# ZOWI_Main_Board_Peripherals.net
KiCad netlist of a schematic drawn in Altium Designer
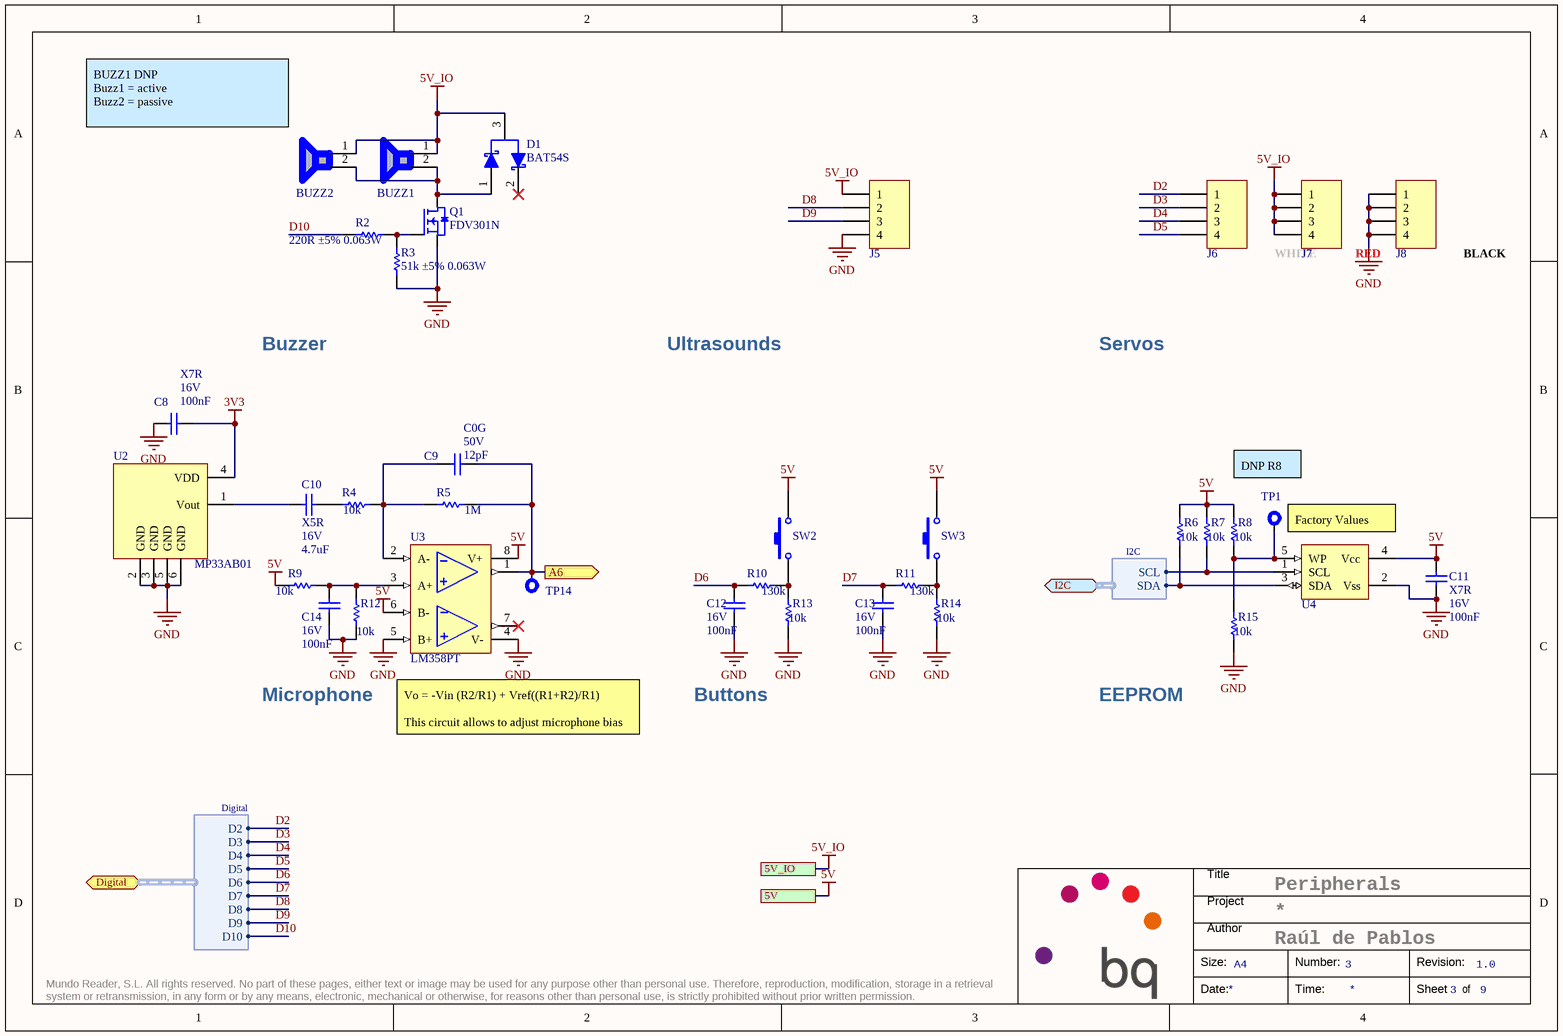
[diagram p0: ZOWI_Main_Board_Peripherals.SchDoc]

(export (version "E")
  (design (tool "Eeschema 10.0.6"))
  (components
    (comp (ref "BUZZ1")
      (value "BUZZER")
      (footprint "KXG1205C")
      (description "Buzzer")
      (fields (field (name "MANUFACTURER") "Kingstate Elect.") (field (name "PART NUMBER") "KXG1205C"))
      (libsource (lib "Electromechanical") (part "BUZZER"))
    )
    (comp (ref "BUZZ2")
      (value "BUZZER")
      (footprint "BUZZER_12")
      (description "Buzzer")
      (fields (field (name "MANUFACTURER") "Kingstate Elect.") (field (name "PART NUMBER") "KXG1205"))
      (libsource (lib "Electromechanical") (part "BUZZER"))
    )
    (comp (ref "C8")
      (value "Capacitor")
      (footprint "C0402")
      (description "Capacitor SMD")
      (fields
        (field (name "DIELECTRIC") "X7R")
        (field (name "VOLTAGE") "16V")
        (field (name "CAPACITANCE") "100nF")
        (field (name "PART NUMBER") "C0402_100nF_16V_±10%")
        (field (name "TOLERANCE") "±10%")
      )
      (libsource (lib "Pasives_Capacitor_SMD") (part "Capacitor"))
    )
    (comp (ref "C9")
      (value "Capacitor")
      (footprint "C0402")
      (description "Capacitor SMD")
      (fields
        (field (name "DIELECTRIC") "C0G")
        (field (name "VOLTAGE") "50V")
        (field (name "CAPACITANCE") "12pF")
        (field (name "PART NUMBER") "C0402_12pF_50V_±5%")
        (field (name "TOLERANCE") "±5%")
      )
      (libsource (lib "Pasives_Capacitor_SMD") (part "Capacitor"))
    )
    (comp (ref "C10")
      (value "Capacitor")
      (footprint "C0603")
      (description "Capacitor SMD")
      (fields
        (field (name "DIELECTRIC") "X5R")
        (field (name "VOLTAGE") "16V")
        (field (name "CAPACITANCE") "4.7uF")
        (field (name "PART NUMBER") "C0603_4.7uF_16V_±10%")
        (field (name "TOLERANCE") "±10%")
      )
      (libsource (lib "Pasives_Capacitor_SMD") (part "Capacitor"))
    )
    (comp (ref "C11")
      (value "Capacitor")
      (footprint "C0402")
      (description "Capacitor SMD")
      (fields
        (field (name "DIELECTRIC") "X7R")
        (field (name "VOLTAGE") "16V")
        (field (name "CAPACITANCE") "100nF")
        (field (name "PART NUMBER") "C0402_100nF_16V_±10%")
        (field (name "TOLERANCE") "±10%")
      )
      (libsource (lib "Pasives_Capacitor_SMD") (part "Capacitor"))
    )
    (comp (ref "C12")
      (value "Capacitor")
      (footprint "C0402")
      (description "Capacitor SMD")
      (fields
        (field (name "VOLTAGE") "16V")
        (field (name "CAPACITANCE") "100nF")
        (field (name "PART NUMBER") "C0402_100nF_16V_±10%")
        (field (name "TOLERANCE") "±10%")
      )
      (libsource (lib "Pasives_Capacitor_SMD") (part "Capacitor"))
    )
    (comp (ref "C13")
      (value "Capacitor")
      (footprint "C0402")
      (description "Capacitor SMD")
      (fields
        (field (name "VOLTAGE") "16V")
        (field (name "CAPACITANCE") "100nF")
        (field (name "PART NUMBER") "C0402_100nF_16V_±10%")
        (field (name "TOLERANCE") "±10%")
      )
      (libsource (lib "Pasives_Capacitor_SMD") (part "Capacitor"))
    )
    (comp (ref "C14")
      (value "Capacitor")
      (footprint "C0402")
      (description "Capacitor SMD")
      (fields
        (field (name "VOLTAGE") "16V")
        (field (name "CAPACITANCE") "100nF")
        (field (name "PART NUMBER") "C0402_100nF_16V_±10%")
        (field (name "TOLERANCE") "±10%")
      )
      (libsource (lib "Pasives_Capacitor_SMD") (part "Capacitor"))
    )
    (comp (ref "D1")
      (value "BAT54S")
      (footprint "SOT23-3")
      (description "Dual Schottky Diode")
      (fields (field (name "MANUFACTURER") "NXP"))
      (libsource (lib "Semiconductors_Diodes") (part "Dual Schottky"))
    )
    (comp (ref "J5")
      (value "1x4 pin Header 2.54mm")
      (footprint "1x4 Pin Header 2.54")
      (description "Connector, 1x4 pin Header 2.54mm")
      (fields (field (name "MANUFACTURER") "Samtec") (field (name "PART NUMBER") "CON_PH_THT2.54_4"))
      (libsource (lib "Conectores_PinHeader_2.54") (part "1x4 pin Header 2.54mm"))
    )
    (comp (ref "J6")
      (value "1x4 pin Header 2.54mm")
      (footprint "1x4 Pin Header 2.54")
      (description "Connector, 1x4 pin Header 2.54mm")
      (fields (field (name "MANUFACTURER") "Samtec") (field (name "PART NUMBER") "CON_PH_THT2.54_4 Natural"))
      (libsource (lib "Conectores_PinHeader_2.54") (part "1x4 pin Header 2.54mm"))
    )
    (comp (ref "J7")
      (value "1x4 pin Header 2.54mm")
      (footprint "1x4 Pin Header 2.54")
      (description "Connector, 1x4 pin Header 2.54mm")
      (fields (field (name "MANUFACTURER") "Samtec") (field (name "PART NUMBER") "CON_PH_THT2.54_4 Red"))
      (libsource (lib "Conectores_PinHeader_2.54") (part "1x4 pin Header 2.54mm"))
    )
    (comp (ref "J8")
      (value "1x4 pin Header 2.54mm")
      (footprint "1x4 Pin Header 2.54")
      (description "Connector, 1x4 pin Header 2.54mm")
      (fields (field (name "MANUFACTURER") "Samtec") (field (name "PART NUMBER") "CON_PH_THT2.54_4"))
      (libsource (lib "Conectores_PinHeader_2.54") (part "1x4 pin Header 2.54mm"))
    )
    (comp (ref "Q1")
      (value "FDV301N")
      (footprint "SOT23-3")
      (description "NFET")
      (fields (field (name "MANUFACTURER") "Fairchild Semiconductor"))
      (libsource (lib "Semiconductors_Transistors") (part "Mosfet_N"))
    )
    (comp (ref "R2")
      (value "220R ±5% 0.063W")
      (footprint "R0402")
      (description "Resistor, SMD")
      (fields (field (name "TOLERANCE") "±5%") (field (name "POWER") "0.063W"))
      (libsource (lib "Pasives_Resistor_SMD") (part "Resistor"))
    )
    (comp (ref "R3")
      (value "51k ±5% 0.063W")
      (footprint "R0402")
      (description "Resistor, SMD")
      (fields (field (name "TOLERANCE") "±5%") (field (name "POWER") "0.063W"))
      (libsource (lib "Pasives_Resistor_SMD") (part "Resistor"))
    )
    (comp (ref "R4")
      (value "Resistor")
      (footprint "R0402")
      (description "Resistor, SMD")
      (fields
        (field (name "TOLERANCE") "±5%")
        (field (name "POWER") "0.063W")
        (field (name "RESISTANCE") "10k")
      )
      (libsource (lib "Pasives_Resistor_SMD") (part "Resistor"))
    )
    (comp (ref "R5")
      (value "Resistor")
      (footprint "R0402")
      (description "Resistor, SMD")
      (fields
        (field (name "TOLERANCE") "±5%")
        (field (name "POWER") "0.063W")
        (field (name "RESISTANCE") "1M")
      )
      (libsource (lib "Pasives_Resistor_SMD") (part "Resistor"))
    )
    (comp (ref "R6")
      (value "Resistor")
      (footprint "R0402")
      (description "Resistor, SMD")
      (fields
        (field (name "TOLERANCE") "±5%")
        (field (name "POWER") "0.063W")
        (field (name "RESISTANCE") "10k")
      )
      (libsource (lib "Pasives_Resistor_SMD") (part "Resistor"))
    )
    (comp (ref "R7")
      (value "Resistor")
      (footprint "R0402")
      (description "Resistor, SMD")
      (fields
        (field (name "TOLERANCE") "±5%")
        (field (name "POWER") "0.063W")
        (field (name "RESISTANCE") "10k")
      )
      (libsource (lib "Pasives_Resistor_SMD") (part "Resistor"))
    )
    (comp (ref "R8")
      (value "Resistor")
      (footprint "R0402")
      (description "Resistor, SMD")
      (fields
        (field (name "TOLERANCE") "±5%")
        (field (name "POWER") "0.063W")
        (field (name "RESISTANCE") "10k")
      )
      (libsource (lib "Pasives_Resistor_SMD") (part "Resistor"))
    )
    (comp (ref "R9")
      (value "Resistor")
      (footprint "R0402")
      (description "Resistor, SMD")
      (fields
        (field (name "TOLERANCE") "±5%")
        (field (name "POWER") "0.063W")
        (field (name "RESISTANCE") "10k")
      )
      (libsource (lib "Pasives_Resistor_SMD") (part "Resistor"))
    )
    (comp (ref "R10")
      (value "Resistor")
      (footprint "R0402")
      (description "Resistor, SMD")
      (fields
        (field (name "TOLERANCE") "±1%")
        (field (name "POWER") "0.063W")
        (field (name "RESISTANCE") "130k")
      )
      (libsource (lib "Pasives_Resistor_SMD") (part "Resistor"))
    )
    (comp (ref "R11")
      (value "Resistor")
      (footprint "R0402")
      (description "Resistor, SMD")
      (fields
        (field (name "TOLERANCE") "±1%")
        (field (name "POWER") "0.063W")
        (field (name "RESISTANCE") "130k")
      )
      (libsource (lib "Pasives_Resistor_SMD") (part "Resistor"))
    )
    (comp (ref "R12")
      (value "Resistor")
      (footprint "R0402")
      (description "Resistor, SMD")
      (fields
        (field (name "TOLERANCE") "±5%")
        (field (name "POWER") "0.063W")
        (field (name "RESISTANCE") "10k")
      )
      (libsource (lib "Pasives_Resistor_SMD") (part "Resistor"))
    )
    (comp (ref "R13")
      (value "Resistor")
      (footprint "R0402")
      (description "Resistor, SMD")
      (fields
        (field (name "TOLERANCE") "±5%")
        (field (name "POWER") "0.063W")
        (field (name "RESISTANCE") "10k")
      )
      (libsource (lib "Pasives_Resistor_SMD") (part "Resistor"))
    )
    (comp (ref "R14")
      (value "Resistor")
      (footprint "R0402")
      (description "Resistor, SMD")
      (fields
        (field (name "TOLERANCE") "±5%")
        (field (name "POWER") "0.063W")
        (field (name "RESISTANCE") "10k")
      )
      (libsource (lib "Pasives_Resistor_SMD") (part "Resistor"))
    )
    (comp (ref "R15")
      (value "Resistor")
      (footprint "R0402")
      (description "Resistor, SMD")
      (fields
        (field (name "TOLERANCE") "±5%")
        (field (name "POWER") "0.063W")
        (field (name "RESISTANCE") "10k")
      )
      (libsource (lib "Pasives_Resistor_SMD") (part "Resistor"))
    )
    (comp (ref "SW2")
      (value "Switch")
      (footprint "MJTP1105T")
      (description "Micro miniature pushbutton surface Switch")
      (fields (field (name "PART NUMBER") "MJTP1105T") (field (name "MANUFACTURER") "APEM"))
      (libsource (lib "Electromechanical") (part "Switch"))
    )
    (comp (ref "SW3")
      (value "Switch")
      (footprint "MJTP1105T")
      (description "Micro miniature pushbutton surface Switch")
      (fields (field (name "PART NUMBER") "MJTP1105T") (field (name "MANUFACTURER") "APEM"))
      (libsource (lib "Electromechanical") (part "Switch"))
    )
    (comp (ref "TP1")
      (value "Testpoint")
      (footprint "TP_SMD_1mm")
      (fields (field (name "MANUFACTURER") "Oxley") (field (name "PART NUMBER") "TP_SMD_1mm"))
      (libsource (lib "Miscelanea") (part "Testpoint"))
    )
    (comp (ref "TP14")
      (value "Testpoint")
      (footprint "TP_SMD_1mm")
      (fields (field (name "MANUFACTURER") "Oxley") (field (name "PART NUMBER") "TP_SMD_1mm"))
      (libsource (lib "Miscelanea") (part "Testpoint"))
    )
    (comp (ref "U2")
      (value "MP33AB01")
      (footprint "RHLGA")
      (description "Microphone MEMS audio surface-mount")
      (fields (field (name "PART NUMBER") "MP33AB01") (field (name "MANUFACTURER") "ST Microelectronics"))
      (libsource (lib "Sensors") (part "MP33AB01"))
    )
    (comp (ref "U3")
      (value "LM358PT")
      (footprint "TSSOP8")
      (description "Operational Amplifier Dual")
      (fields
        (field (name "PART NUMBER") "LM358")
        (field (name "ORDERINGCODE") "LM358PT")
        (field (name "MANUFACTURER") "ST")
      )
      (libsource (lib "Semiconductors_OA") (part "LM358"))
    )
    (comp (ref "U4")
      (value "24AA01")
      (footprint "SOT23-5")
      (description "EEPROM Memory I2C 1KBIT 400KHZ SOT23-5")
      (fields (field (name "PART NUMBER") "24AA01T-I/OT") (field (name "MANUFACTURER") "Microchip"))
      (libsource (lib "Memory_Serial") (part "24AA01"))
    )
  )
  (nets
    (net (code "3") (name "/A6") (class "Default")
      (node (ref "C9") (pin "2") (pinfunction "2_2") (pintype "passive"))
      (node (ref "R5") (pin "2") (pinfunction "2_2") (pintype "passive"))
      (node (ref "TP14") (pin "1") (pinfunction "1_1") (pintype "passive"))
      (node (ref "U3") (pin "1") (pinfunction "Out_1") (pintype "output"))
    )
    (net (code "4") (name "/D2") (class "Default")
      (node (ref "J6") (pin "1") (pinfunction "1_1") (pintype "passive"))
    )
    (net (code "5") (name "/D3") (class "Default")
      (node (ref "J6") (pin "2") (pinfunction "2_2") (pintype "passive"))
    )
    (net (code "6") (name "/D4") (class "Default")
      (node (ref "J6") (pin "3") (pinfunction "3_3") (pintype "passive"))
    )
    (net (code "7") (name "/D5") (class "Default")
      (node (ref "J6") (pin "4") (pinfunction "4_4") (pintype "passive"))
    )
    (net (code "8") (name "/D6") (class "Default")
      (node (ref "C12") (pin "2") (pinfunction "2_2") (pintype "passive"))
      (node (ref "R10") (pin "2") (pinfunction "2_2") (pintype "passive"))
    )
    (net (code "9") (name "/D7") (class "Default")
      (node (ref "C13") (pin "2") (pinfunction "2_2") (pintype "passive"))
      (node (ref "R11") (pin "2") (pinfunction "2_2") (pintype "passive"))
    )
    (net (code "10") (name "/D8") (class "Default")
      (node (ref "J5") (pin "2") (pinfunction "2_2") (pintype "passive"))
    )
    (net (code "11") (name "/D9") (class "Default")
      (node (ref "J5") (pin "3") (pinfunction "3_3") (pintype "passive"))
    )
    (net (code "12") (name "/D10") (class "Default")
      (node (ref "R2") (pin "1") (pinfunction "1_1") (pintype "passive"))
    )
    (net (code "15") (name "3V3") (class "Default")
      (node (ref "C8") (pin "1") (pinfunction "1_1") (pintype "passive"))
      (node (ref "U2") (pin "4") (pinfunction "VDD_4") (pintype "power_in"))
    )
    (net (code "16") (name "5V") (class "Default")
      (node (ref "C11") (pin "2") (pinfunction "2_2") (pintype "passive"))
      (node (ref "R6") (pin "2") (pinfunction "2_2") (pintype "passive"))
      (node (ref "R7") (pin "2") (pinfunction "2_2") (pintype "passive"))
      (node (ref "R8") (pin "2") (pinfunction "2_2") (pintype "passive"))
      (node (ref "R9") (pin "1") (pinfunction "1_1") (pintype "passive"))
      (node (ref "SW2") (pin "2") (pinfunction "2_2") (pintype "passive"))
      (node (ref "SW3") (pin "2") (pinfunction "2_2") (pintype "passive"))
      (node (ref "U3") (pin "6") (pinfunction "B-_6") (pintype "input"))
      (node (ref "U3") (pin "8") (pinfunction "V+_8") (pintype "power_in"))
      (node (ref "U4") (pin "4") (pinfunction "Vcc_4") (pintype "power_in"))
    )
    (net (code "17") (name "5V_IO") (class "Default")
      (node (ref "BUZZ1") (pin "1") (pinfunction "1_1") (pintype "passive"))
      (node (ref "BUZZ2") (pin "1") (pinfunction "1_1") (pintype "passive"))
      (node (ref "D1") (pin "3") (pinfunction "K1_3") (pintype "passive"))
      (node (ref "J5") (pin "1") (pinfunction "1_1") (pintype "passive"))
      (node (ref "J7") (pin "1") (pinfunction "1_1") (pintype "passive"))
      (node (ref "J7") (pin "2") (pinfunction "2_2") (pintype "passive"))
      (node (ref "J7") (pin "3") (pinfunction "3_3") (pintype "passive"))
      (node (ref "J7") (pin "4") (pinfunction "4_4") (pintype "passive"))
    )
    (net (code "18") (name "GND") (class "Default")
      (node (ref "C11") (pin "1") (pinfunction "1_1") (pintype "passive"))
      (node (ref "C12") (pin "1") (pinfunction "1_1") (pintype "passive"))
      (node (ref "C13") (pin "1") (pinfunction "1_1") (pintype "passive"))
      (node (ref "C14") (pin "1") (pinfunction "1_1") (pintype "passive"))
      (node (ref "C8") (pin "2") (pinfunction "2_2") (pintype "passive"))
      (node (ref "J5") (pin "4") (pinfunction "4_4") (pintype "passive"))
      (node (ref "J8") (pin "1") (pinfunction "1_1") (pintype "passive"))
      (node (ref "J8") (pin "2") (pinfunction "2_2") (pintype "passive"))
      (node (ref "J8") (pin "3") (pinfunction "3_3") (pintype "passive"))
      (node (ref "J8") (pin "4") (pinfunction "4_4") (pintype "passive"))
      (node (ref "Q1") (pin "2") (pinfunction "S_2") (pintype "passive"))
      (node (ref "R12") (pin "1") (pinfunction "1_1") (pintype "passive"))
      (node (ref "R13") (pin "1") (pinfunction "1_1") (pintype "passive"))
      (node (ref "R14") (pin "1") (pinfunction "1_1") (pintype "passive"))
      (node (ref "R15") (pin "1") (pinfunction "1_1") (pintype "passive"))
      (node (ref "R3") (pin "1") (pinfunction "1_1") (pintype "passive"))
      (node (ref "U2") (pin "2") (pinfunction "GND_2") (pintype "power_in"))
      (node (ref "U2") (pin "3") (pinfunction "GND_3") (pintype "power_in"))
      (node (ref "U2") (pin "5") (pinfunction "GND_5") (pintype "power_in"))
      (node (ref "U2") (pin "6") (pinfunction "GND_6") (pintype "power_in"))
      (node (ref "U3") (pin "4") (pinfunction "V-_4") (pintype "power_in"))
      (node (ref "U3") (pin "5") (pinfunction "B+_5") (pintype "input"))
      (node (ref "U4") (pin "2") (pinfunction "Vss_2") (pintype "power_in"))
    )
    (net (code "19") (name "Net-(C10-Pad2)") (class "Default")
      (node (ref "C10") (pin "2") (pinfunction "2_2") (pintype "passive"))
      (node (ref "R4") (pin "1") (pinfunction "1_1") (pintype "passive"))
    )
    (net (code "20") (name "Net-(D1-A)") (class "Default")
      (node (ref "BUZZ1") (pin "2") (pinfunction "2_2") (pintype "passive"))
      (node (ref "BUZZ2") (pin "2") (pinfunction "2_2") (pintype "passive"))
      (node (ref "D1") (pin "1") (pinfunction "A_1") (pintype "passive"))
      (node (ref "Q1") (pin "3") (pinfunction "D_3") (pintype "passive"))
    )
    (net (code "21") (name "Net-(Q1-G)") (class "Default")
      (node (ref "Q1") (pin "1") (pinfunction "G_1") (pintype "passive"))
      (node (ref "R2") (pin "2") (pinfunction "2_2") (pintype "passive"))
      (node (ref "R3") (pin "2") (pinfunction "2_2") (pintype "passive"))
    )
    (net (code "22") (name "Net-(R10-Pad1)") (class "Default")
      (node (ref "R10") (pin "1") (pinfunction "1_1") (pintype "passive"))
      (node (ref "R13") (pin "2") (pinfunction "2_2") (pintype "passive"))
      (node (ref "SW2") (pin "1") (pinfunction "1_1") (pintype "passive"))
    )
    (net (code "23") (name "Net-(R11-Pad1)") (class "Default")
      (node (ref "R11") (pin "1") (pinfunction "1_1") (pintype "passive"))
      (node (ref "R14") (pin "2") (pinfunction "2_2") (pintype "passive"))
      (node (ref "SW3") (pin "1") (pinfunction "1_1") (pintype "passive"))
    )
    (net (code "24") (name "Net-(U2-Vout)") (class "Default")
      (node (ref "C10") (pin "1") (pinfunction "1_1") (pintype "passive"))
      (node (ref "U2") (pin "1") (pinfunction "Vout_1") (pintype "power_in"))
    )
    (net (code "25") (name "Net-(U3-A+)") (class "Default")
      (node (ref "C14") (pin "2") (pinfunction "2_2") (pintype "passive"))
      (node (ref "R12") (pin "2") (pinfunction "2_2") (pintype "passive"))
      (node (ref "R9") (pin "2") (pinfunction "2_2") (pintype "passive"))
      (node (ref "U3") (pin "3") (pinfunction "A+_3") (pintype "input"))
    )
    (net (code "26") (name "Net-(U3-A-)") (class "Default")
      (node (ref "C9") (pin "1") (pinfunction "1_1") (pintype "passive"))
      (node (ref "R4") (pin "2") (pinfunction "2_2") (pintype "passive"))
      (node (ref "R5") (pin "1") (pinfunction "1_1") (pintype "passive"))
      (node (ref "U3") (pin "2") (pinfunction "A-_2") (pintype "input"))
    )
    (net (code "27") (name "Net-(U4-SCL)") (class "Default")
      (node (ref "R7") (pin "1") (pinfunction "1_1") (pintype "passive"))
      (node (ref "U4") (pin "1") (pinfunction "SCL_1") (pintype "input"))
    )
    (net (code "28") (name "Net-(U4-SDA)") (class "Default")
      (node (ref "R6") (pin "1") (pinfunction "1_1") (pintype "passive"))
      (node (ref "U4") (pin "3") (pinfunction "SDA_3") (pintype "bidirectional"))
    )
    (net (code "29") (name "Net-(U4-WP)") (class "Default")
      (node (ref "R15") (pin "2") (pinfunction "2_2") (pintype "passive"))
      (node (ref "R8") (pin "1") (pinfunction "1_1") (pintype "passive"))
      (node (ref "TP1") (pin "1") (pinfunction "1_1") (pintype "passive"))
      (node (ref "U4") (pin "5") (pinfunction "WP_5") (pintype "input"))
    )
    (net (code "30") (name "unconnected-(D1-K2-Pad2)") (class "Default")
      (node (ref "D1") (pin "2") (pinfunction "K2_2") (pintype "passive+no_connect"))
    )
    (net (code "31") (name "unconnected-(U3-Out2-Pad7)") (class "Default")
      (node (ref "U3") (pin "7") (pinfunction "Out2_7") (pintype "output+no_connect"))
    )
  )
)
